# DLS_1_0.net
KiCad netlist of a schematic drawn in EAGLE
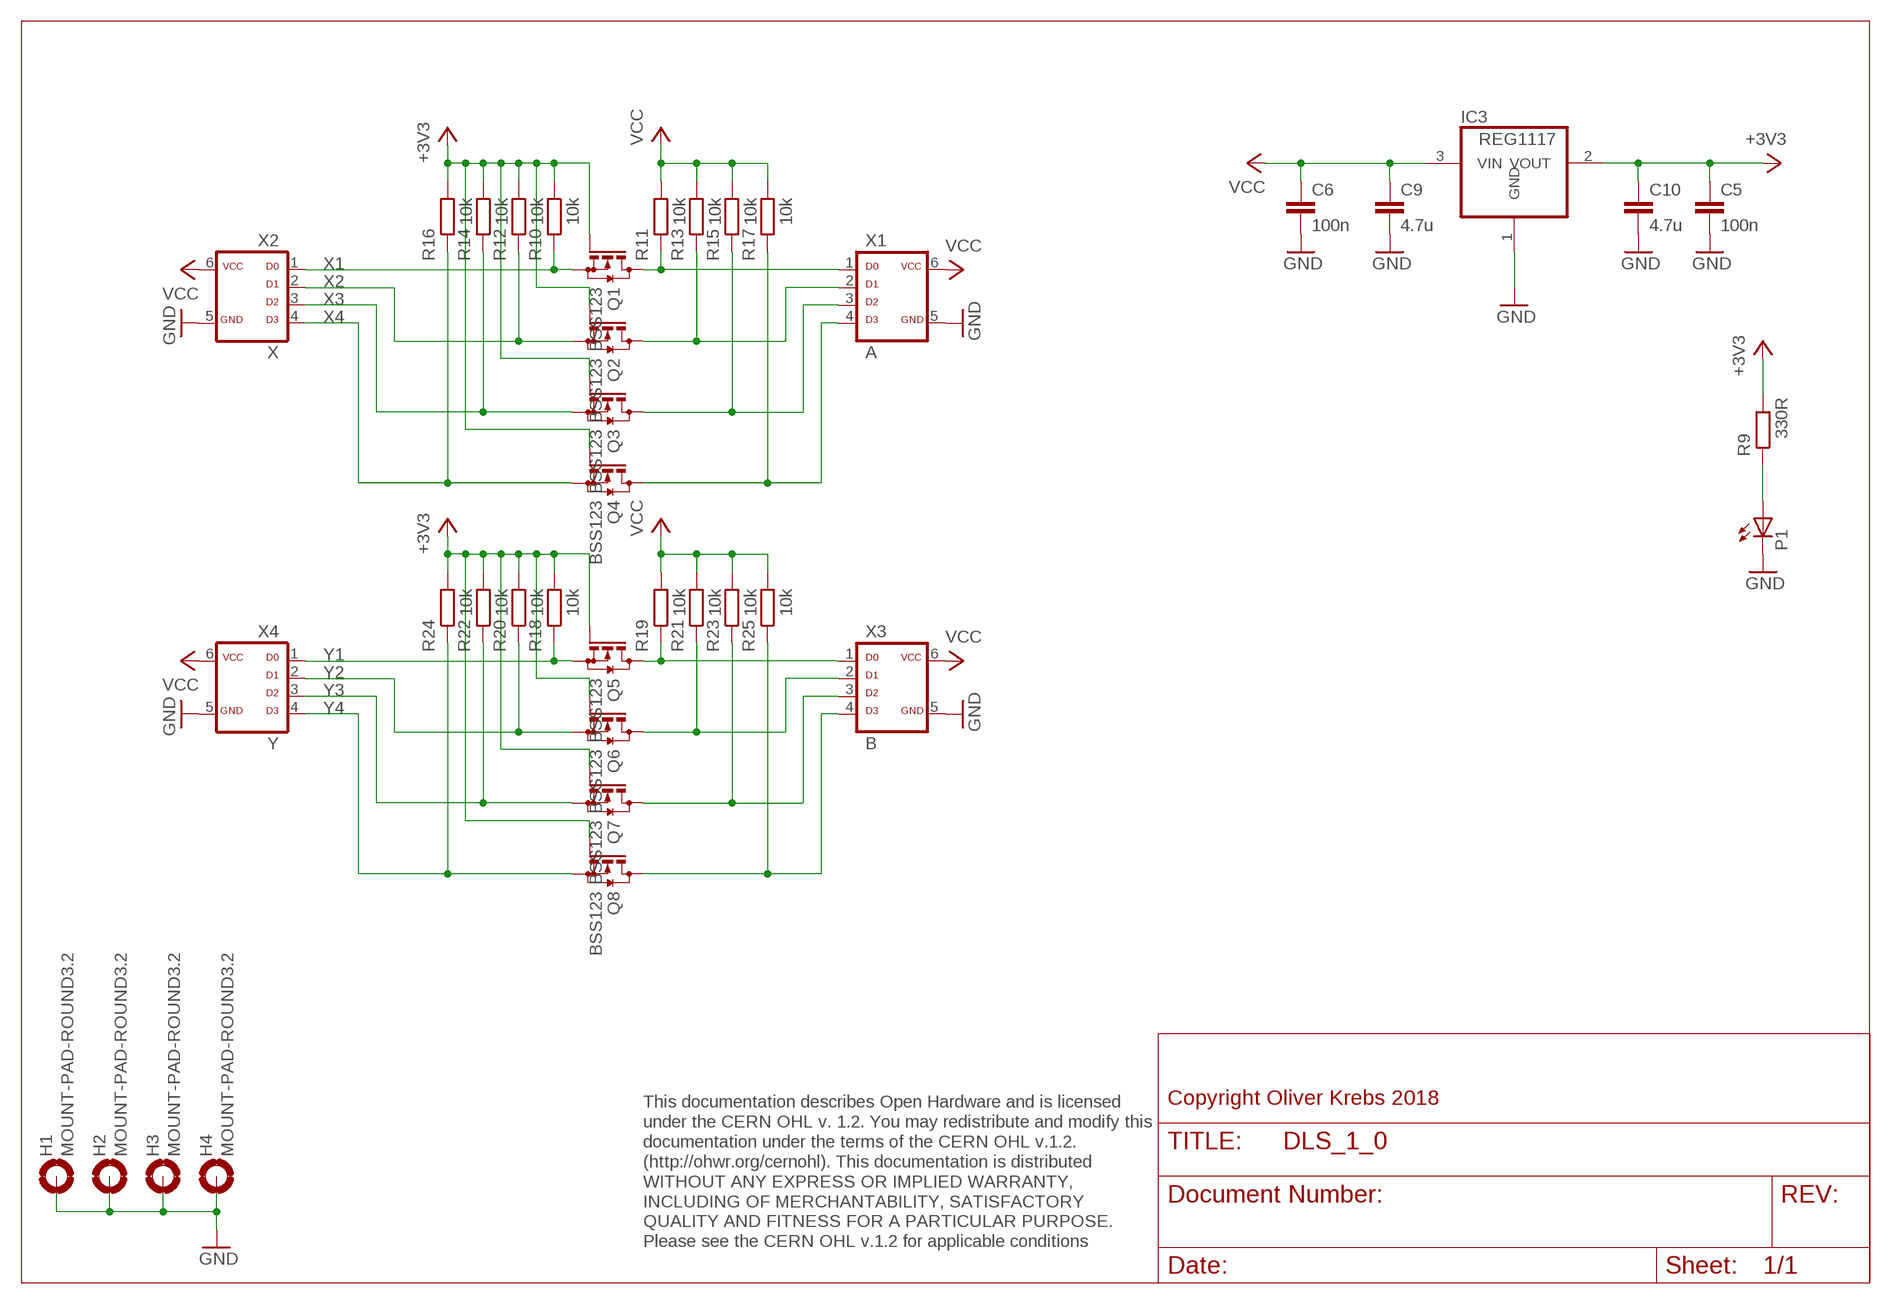
[diagram p0: schematic, sheet 1]

(export (version "E")
  (design (tool "Eeschema 10.0.6"))
  (components
    (comp (ref "C5")
      (value "100n")
      (footprint "eagle-import:C0603")
      (libsource (lib "eagle-import") (part "C-EUC0603"))
    )
    (comp (ref "C6")
      (value "100n")
      (footprint "eagle-import:C0603")
      (libsource (lib "eagle-import") (part "C-EUC0603"))
    )
    (comp (ref "C9")
      (value "4.7u")
      (footprint "eagle-import:C0805K")
      (libsource (lib "eagle-import") (part "C-EUC0805K"))
    )
    (comp (ref "C10")
      (value "4.7u")
      (footprint "eagle-import:C0805K")
      (libsource (lib "eagle-import") (part "C-EUC0805K"))
    )
    (comp (ref "H1")
      (value "MOUNT-PAD-ROUND3.2")
      (footprint "eagle-import:3,2-PAD")
      (libsource (lib "eagle-import") (part "MOUNT-PAD-ROUND3.2"))
    )
    (comp (ref "H2")
      (value "MOUNT-PAD-ROUND3.2")
      (footprint "eagle-import:3,2-PAD")
      (libsource (lib "eagle-import") (part "MOUNT-PAD-ROUND3.2"))
    )
    (comp (ref "H3")
      (value "MOUNT-PAD-ROUND3.2")
      (footprint "eagle-import:3,2-PAD")
      (libsource (lib "eagle-import") (part "MOUNT-PAD-ROUND3.2"))
    )
    (comp (ref "H4")
      (value "MOUNT-PAD-ROUND3.2")
      (footprint "eagle-import:3,2-PAD")
      (libsource (lib "eagle-import") (part "MOUNT-PAD-ROUND3.2"))
    )
    (comp (ref "IC3")
      (value "REG1117")
      (footprint "eagle-import:SOT223")
      (libsource (lib "eagle-import") (part "REG1117"))
    )
    (comp (ref "P1")
      (value "LEDCHIPLED_1206")
      (footprint "eagle-import:CHIPLED_1206")
      (libsource (lib "eagle-import") (part "LEDCHIPLED_1206"))
    )
    (comp (ref "Q1")
      (value "BSS123")
      (footprint "eagle-import:SOT23")
      (libsource (lib "eagle-import") (part "BSS123"))
    )
    (comp (ref "Q2")
      (value "BSS123")
      (footprint "eagle-import:SOT23")
      (libsource (lib "eagle-import") (part "BSS123"))
    )
    (comp (ref "Q3")
      (value "BSS123")
      (footprint "eagle-import:SOT23")
      (libsource (lib "eagle-import") (part "BSS123"))
    )
    (comp (ref "Q4")
      (value "BSS123")
      (footprint "eagle-import:SOT23")
      (libsource (lib "eagle-import") (part "BSS123"))
    )
    (comp (ref "Q5")
      (value "BSS123")
      (footprint "eagle-import:SOT23")
      (libsource (lib "eagle-import") (part "BSS123"))
    )
    (comp (ref "Q6")
      (value "BSS123")
      (footprint "eagle-import:SOT23")
      (libsource (lib "eagle-import") (part "BSS123"))
    )
    (comp (ref "Q7")
      (value "BSS123")
      (footprint "eagle-import:SOT23")
      (libsource (lib "eagle-import") (part "BSS123"))
    )
    (comp (ref "Q8")
      (value "BSS123")
      (footprint "eagle-import:SOT23")
      (libsource (lib "eagle-import") (part "BSS123"))
    )
    (comp (ref "R9")
      (value "330R")
      (footprint "eagle-import:R0402")
      (libsource (lib "eagle-import") (part "R-EU_R0402"))
    )
    (comp (ref "R10")
      (value "10k")
      (footprint "eagle-import:R0402")
      (libsource (lib "eagle-import") (part "R-EU_R0402"))
    )
    (comp (ref "R11")
      (value "10k")
      (footprint "eagle-import:R0402")
      (libsource (lib "eagle-import") (part "R-EU_R0402"))
    )
    (comp (ref "R12")
      (value "10k")
      (footprint "eagle-import:R0402")
      (libsource (lib "eagle-import") (part "R-EU_R0402"))
    )
    (comp (ref "R13")
      (value "10k")
      (footprint "eagle-import:R0402")
      (libsource (lib "eagle-import") (part "R-EU_R0402"))
    )
    (comp (ref "R14")
      (value "10k")
      (footprint "eagle-import:R0402")
      (libsource (lib "eagle-import") (part "R-EU_R0402"))
    )
    (comp (ref "R15")
      (value "10k")
      (footprint "eagle-import:R0402")
      (libsource (lib "eagle-import") (part "R-EU_R0402"))
    )
    (comp (ref "R16")
      (value "10k")
      (footprint "eagle-import:R0402")
      (libsource (lib "eagle-import") (part "R-EU_R0402"))
    )
    (comp (ref "R17")
      (value "10k")
      (footprint "eagle-import:R0402")
      (libsource (lib "eagle-import") (part "R-EU_R0402"))
    )
    (comp (ref "R18")
      (value "10k")
      (footprint "eagle-import:R0402")
      (libsource (lib "eagle-import") (part "R-EU_R0402"))
    )
    (comp (ref "R19")
      (value "10k")
      (footprint "eagle-import:R0402")
      (libsource (lib "eagle-import") (part "R-EU_R0402"))
    )
    (comp (ref "R20")
      (value "10k")
      (footprint "eagle-import:R0402")
      (libsource (lib "eagle-import") (part "R-EU_R0402"))
    )
    (comp (ref "R21")
      (value "10k")
      (footprint "eagle-import:R0402")
      (libsource (lib "eagle-import") (part "R-EU_R0402"))
    )
    (comp (ref "R22")
      (value "10k")
      (footprint "eagle-import:R0402")
      (libsource (lib "eagle-import") (part "R-EU_R0402"))
    )
    (comp (ref "R23")
      (value "10k")
      (footprint "eagle-import:R0402")
      (libsource (lib "eagle-import") (part "R-EU_R0402"))
    )
    (comp (ref "R24")
      (value "10k")
      (footprint "eagle-import:R0402")
      (libsource (lib "eagle-import") (part "R-EU_R0402"))
    )
    (comp (ref "R25")
      (value "10k")
      (footprint "eagle-import:R0402")
      (libsource (lib "eagle-import") (part "R-EU_R0402"))
    )
    (comp (ref "X1")
      (value "A")
      (footprint "eagle-import:ML-6")
      (libsource (lib "eagle-import") (part "ML6D"))
    )
    (comp (ref "X2")
      (value "X")
      (footprint "eagle-import:ML-6")
      (libsource (lib "eagle-import") (part "ML6D"))
    )
    (comp (ref "X3")
      (value "B")
      (footprint "eagle-import:ML-6")
      (libsource (lib "eagle-import") (part "ML6D"))
    )
    (comp (ref "X4")
      (value "Y")
      (footprint "eagle-import:ML-6")
      (libsource (lib "eagle-import") (part "ML6D"))
    )
  )
  (nets
    (net (code "1") (name "+3V3") (class "Default")
      (node (ref "C10") (pin "1") (pinfunction "1_1") (pintype "passive"))
      (node (ref "C5") (pin "1") (pinfunction "1_1") (pintype "passive"))
      (node (ref "IC3") (pin "2") (pinfunction "VOUT_2") (pintype "output"))
      (node (ref "Q1") (pin "1") (pinfunction "G_1") (pintype "passive"))
      (node (ref "Q2") (pin "1") (pinfunction "G_1") (pintype "passive"))
      (node (ref "Q3") (pin "1") (pinfunction "G_1") (pintype "passive"))
      (node (ref "Q4") (pin "1") (pinfunction "G_1") (pintype "passive"))
      (node (ref "Q5") (pin "1") (pinfunction "G_1") (pintype "passive"))
      (node (ref "Q6") (pin "1") (pinfunction "G_1") (pintype "passive"))
      (node (ref "Q7") (pin "1") (pinfunction "G_1") (pintype "passive"))
      (node (ref "Q8") (pin "1") (pinfunction "G_1") (pintype "passive"))
      (node (ref "R10") (pin "2") (pinfunction "2_2") (pintype "passive"))
      (node (ref "R12") (pin "2") (pinfunction "2_2") (pintype "passive"))
      (node (ref "R14") (pin "2") (pinfunction "2_2") (pintype "passive"))
      (node (ref "R16") (pin "2") (pinfunction "2_2") (pintype "passive"))
      (node (ref "R18") (pin "2") (pinfunction "2_2") (pintype "passive"))
      (node (ref "R20") (pin "2") (pinfunction "2_2") (pintype "passive"))
      (node (ref "R22") (pin "2") (pinfunction "2_2") (pintype "passive"))
      (node (ref "R24") (pin "2") (pinfunction "2_2") (pintype "passive"))
      (node (ref "R9") (pin "2") (pinfunction "2_2") (pintype "passive"))
    )
    (net (code "2") (name "/X1") (class "Default")
      (node (ref "Q1") (pin "2") (pinfunction "S_2") (pintype "passive"))
      (node (ref "R10") (pin "1") (pinfunction "1_1") (pintype "passive"))
      (node (ref "X2") (pin "1") (pinfunction "1_1") (pintype "passive"))
    )
    (net (code "3") (name "/X2") (class "Default")
      (node (ref "Q2") (pin "2") (pinfunction "S_2") (pintype "passive"))
      (node (ref "R12") (pin "1") (pinfunction "1_1") (pintype "passive"))
      (node (ref "X2") (pin "2") (pinfunction "2_2") (pintype "passive"))
    )
    (net (code "4") (name "/X3") (class "Default")
      (node (ref "Q3") (pin "2") (pinfunction "S_2") (pintype "passive"))
      (node (ref "R14") (pin "1") (pinfunction "1_1") (pintype "passive"))
      (node (ref "X2") (pin "3") (pinfunction "3_3") (pintype "passive"))
    )
    (net (code "5") (name "/X4") (class "Default")
      (node (ref "Q4") (pin "2") (pinfunction "S_2") (pintype "passive"))
      (node (ref "R16") (pin "1") (pinfunction "1_1") (pintype "passive"))
      (node (ref "X2") (pin "4") (pinfunction "4_4") (pintype "passive"))
    )
    (net (code "6") (name "/Y1") (class "Default")
      (node (ref "Q5") (pin "2") (pinfunction "S_2") (pintype "passive"))
      (node (ref "R18") (pin "1") (pinfunction "1_1") (pintype "passive"))
      (node (ref "X4") (pin "1") (pinfunction "1_1") (pintype "passive"))
    )
    (net (code "7") (name "/Y2") (class "Default")
      (node (ref "Q6") (pin "2") (pinfunction "S_2") (pintype "passive"))
      (node (ref "R20") (pin "1") (pinfunction "1_1") (pintype "passive"))
      (node (ref "X4") (pin "2") (pinfunction "2_2") (pintype "passive"))
    )
    (net (code "8") (name "/Y3") (class "Default")
      (node (ref "Q7") (pin "2") (pinfunction "S_2") (pintype "passive"))
      (node (ref "R22") (pin "1") (pinfunction "1_1") (pintype "passive"))
      (node (ref "X4") (pin "3") (pinfunction "3_3") (pintype "passive"))
    )
    (net (code "9") (name "/Y4") (class "Default")
      (node (ref "Q8") (pin "2") (pinfunction "S_2") (pintype "passive"))
      (node (ref "R24") (pin "1") (pinfunction "1_1") (pintype "passive"))
      (node (ref "X4") (pin "4") (pinfunction "4_4") (pintype "passive"))
    )
    (net (code "10") (name "GND") (class "Default")
      (node (ref "C10") (pin "2") (pinfunction "2_2") (pintype "passive"))
      (node (ref "C5") (pin "2") (pinfunction "2_2") (pintype "passive"))
      (node (ref "C6") (pin "2") (pinfunction "2_2") (pintype "passive"))
      (node (ref "C9") (pin "2") (pinfunction "2_2") (pintype "passive"))
      (node (ref "H1") (pin "B3,2") (pinfunction "MOUNT_B3,2") (pintype "passive"))
      (node (ref "H2") (pin "B3,2") (pinfunction "MOUNT_B3,2") (pintype "passive"))
      (node (ref "H3") (pin "B3,2") (pinfunction "MOUNT_B3,2") (pintype "passive"))
      (node (ref "H4") (pin "B3,2") (pinfunction "MOUNT_B3,2") (pintype "passive"))
      (node (ref "IC3") (pin "1") (pinfunction "GND_1") (pintype "power_in"))
      (node (ref "P1") (pin "C") (pinfunction "C_C") (pintype "passive"))
      (node (ref "X1") (pin "5") (pinfunction "5_5") (pintype "passive"))
      (node (ref "X2") (pin "5") (pinfunction "5_5") (pintype "passive"))
      (node (ref "X3") (pin "5") (pinfunction "5_5") (pintype "passive"))
      (node (ref "X4") (pin "5") (pinfunction "5_5") (pintype "passive"))
    )
    (net (code "11") (name "Net-(P1-PadA)") (class "Default")
      (node (ref "P1") (pin "A") (pinfunction "A_A") (pintype "passive"))
      (node (ref "R9") (pin "1") (pinfunction "1_1") (pintype "passive"))
    )
    (net (code "12") (name "Net-(Q1-D)") (class "Default")
      (node (ref "Q1") (pin "3") (pinfunction "D_3") (pintype "passive"))
      (node (ref "R11") (pin "1") (pinfunction "1_1") (pintype "passive"))
      (node (ref "X1") (pin "1") (pinfunction "1_1") (pintype "passive"))
    )
    (net (code "13") (name "Net-(Q2-D)") (class "Default")
      (node (ref "Q2") (pin "3") (pinfunction "D_3") (pintype "passive"))
      (node (ref "R13") (pin "1") (pinfunction "1_1") (pintype "passive"))
      (node (ref "X1") (pin "2") (pinfunction "2_2") (pintype "passive"))
    )
    (net (code "14") (name "Net-(Q3-D)") (class "Default")
      (node (ref "Q3") (pin "3") (pinfunction "D_3") (pintype "passive"))
      (node (ref "R15") (pin "1") (pinfunction "1_1") (pintype "passive"))
      (node (ref "X1") (pin "3") (pinfunction "3_3") (pintype "passive"))
    )
    (net (code "15") (name "Net-(Q4-D)") (class "Default")
      (node (ref "Q4") (pin "3") (pinfunction "D_3") (pintype "passive"))
      (node (ref "R17") (pin "1") (pinfunction "1_1") (pintype "passive"))
      (node (ref "X1") (pin "4") (pinfunction "4_4") (pintype "passive"))
    )
    (net (code "16") (name "Net-(Q5-D)") (class "Default")
      (node (ref "Q5") (pin "3") (pinfunction "D_3") (pintype "passive"))
      (node (ref "R19") (pin "1") (pinfunction "1_1") (pintype "passive"))
      (node (ref "X3") (pin "1") (pinfunction "1_1") (pintype "passive"))
    )
    (net (code "17") (name "Net-(Q6-D)") (class "Default")
      (node (ref "Q6") (pin "3") (pinfunction "D_3") (pintype "passive"))
      (node (ref "R21") (pin "1") (pinfunction "1_1") (pintype "passive"))
      (node (ref "X3") (pin "2") (pinfunction "2_2") (pintype "passive"))
    )
    (net (code "18") (name "Net-(Q7-D)") (class "Default")
      (node (ref "Q7") (pin "3") (pinfunction "D_3") (pintype "passive"))
      (node (ref "R23") (pin "1") (pinfunction "1_1") (pintype "passive"))
      (node (ref "X3") (pin "3") (pinfunction "3_3") (pintype "passive"))
    )
    (net (code "19") (name "Net-(Q8-D)") (class "Default")
      (node (ref "Q8") (pin "3") (pinfunction "D_3") (pintype "passive"))
      (node (ref "R25") (pin "1") (pinfunction "1_1") (pintype "passive"))
      (node (ref "X3") (pin "4") (pinfunction "4_4") (pintype "passive"))
    )
    (net (code "20") (name "VCC") (class "Default")
      (node (ref "C6") (pin "1") (pinfunction "1_1") (pintype "passive"))
      (node (ref "C9") (pin "1") (pinfunction "1_1") (pintype "passive"))
      (node (ref "IC3") (pin "3") (pinfunction "VIN_3") (pintype "input"))
      (node (ref "R11") (pin "2") (pinfunction "2_2") (pintype "passive"))
      (node (ref "R13") (pin "2") (pinfunction "2_2") (pintype "passive"))
      (node (ref "R15") (pin "2") (pinfunction "2_2") (pintype "passive"))
      (node (ref "R17") (pin "2") (pinfunction "2_2") (pintype "passive"))
      (node (ref "R19") (pin "2") (pinfunction "2_2") (pintype "passive"))
      (node (ref "R21") (pin "2") (pinfunction "2_2") (pintype "passive"))
      (node (ref "R23") (pin "2") (pinfunction "2_2") (pintype "passive"))
      (node (ref "R25") (pin "2") (pinfunction "2_2") (pintype "passive"))
      (node (ref "X1") (pin "6") (pinfunction "6_6") (pintype "passive"))
      (node (ref "X2") (pin "6") (pinfunction "6_6") (pintype "passive"))
      (node (ref "X3") (pin "6") (pinfunction "6_6") (pintype "passive"))
      (node (ref "X4") (pin "6") (pinfunction "6_6") (pintype "passive"))
    )
  )
)
